# v1.net
KiCad netlist of a schematic drawn in EAGLE
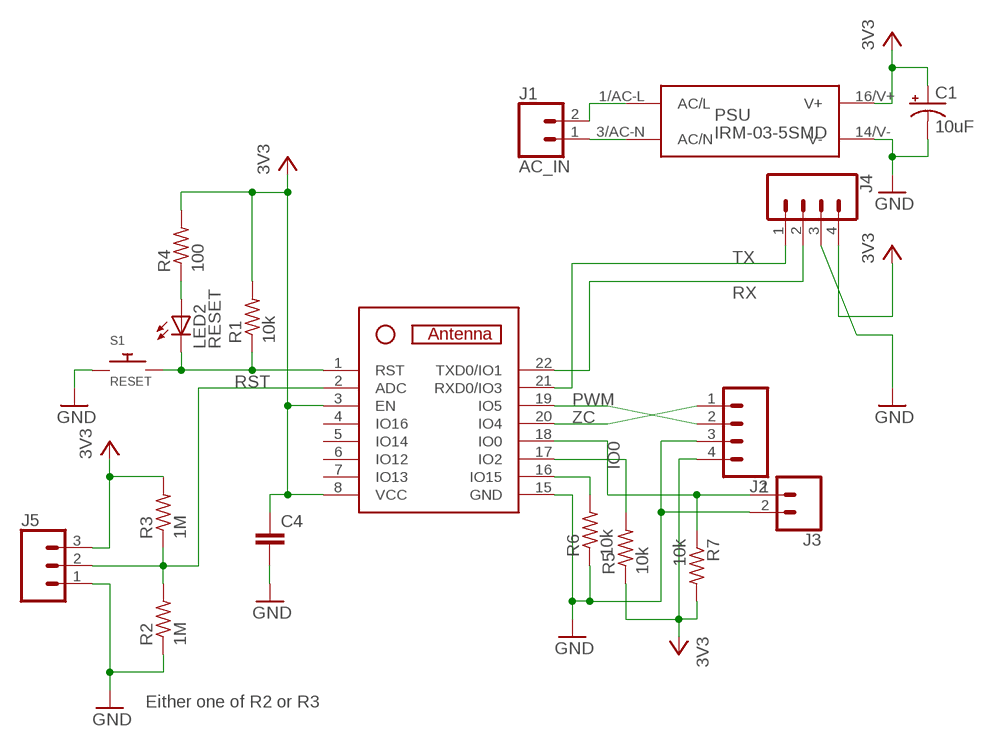
[diagram p0: schematic, sheet 1]

(export (version "E")
  (design (tool "Eeschema 10.0.6"))
  (components
    (comp (ref "C1")
      (value "10uF")
      (footprint "eagle-import:153CLV-0405")
      (libsource (lib "eagle-import") (part "CPOL-US153CLV-0405"))
    )
    (comp (ref "C4")
      (value "C-EUC0805")
      (footprint "eagle-import:C0805")
      (libsource (lib "eagle-import") (part "C-EUC0805"))
    )
    (comp (ref "J1")
      (value "AC_IN")
      (footprint "eagle-import:1X2_5MM_SCREW")
      (libsource (lib "eagle-import") (part "1X2_5MM_SCREW"))
    )
    (comp (ref "J2")
      (value "CONN_04")
      (footprint "eagle-import:1X04")
      (libsource (lib "eagle-import") (part "CONN_04"))
    )
    (comp (ref "J3")
      (value "CONN_02")
      (footprint "eagle-import:1X02")
      (libsource (lib "eagle-import") (part "CONN_02"))
    )
    (comp (ref "J4")
      (value "CONN_04")
      (footprint "eagle-import:1X04")
      (libsource (lib "eagle-import") (part "CONN_04"))
    )
    (comp (ref "J5")
      (value "CONN_03")
      (footprint "eagle-import:1X03")
      (libsource (lib "eagle-import") (part "CONN_03"))
    )
    (comp (ref "LED2")
      (value "RESET")
      (footprint "eagle-import:SML0805")
      (libsource (lib "eagle-import") (part "LEDSML0805"))
    )
    (comp (ref "PSU")
      (value "IRM-03-5SMD")
      (footprint "eagle-import:IRM-03-5S")
      (libsource (lib "eagle-import") (part "IRM-03-5SMD"))
    )
    (comp (ref "R1")
      (value "10k")
      (footprint "eagle-import:R0603")
      (libsource (lib "eagle-import") (part "R-US_R0603"))
    )
    (comp (ref "R2")
      (value "1M")
      (footprint "eagle-import:R0603")
      (libsource (lib "eagle-import") (part "R-US_R0603"))
    )
    (comp (ref "R3")
      (value "1M")
      (footprint "eagle-import:R0603")
      (libsource (lib "eagle-import") (part "R-US_R0603"))
    )
    (comp (ref "R4")
      (value "100")
      (footprint "eagle-import:R0805")
      (libsource (lib "eagle-import") (part "R-US_R0805"))
    )
    (comp (ref "R5")
      (value "10k")
      (footprint "eagle-import:R0603")
      (libsource (lib "eagle-import") (part "R-US_R0603"))
    )
    (comp (ref "R6")
      (value "10k")
      (footprint "eagle-import:R0603")
      (libsource (lib "eagle-import") (part "R-US_R0603"))
    )
    (comp (ref "R7")
      (value "10k")
      (footprint "eagle-import:R0603")
      (libsource (lib "eagle-import") (part "R-US_R0603"))
    )
    (comp (ref "S1")
      (value "RESET")
      (footprint "eagle-import:SMD_BUTTON")
      (libsource (lib "eagle-import") (part "BUTTONSMD"))
    )
    (comp (ref "U1")
      (value "ESP-07")
      (footprint "eagle-import:ESP-07")
      (libsource (lib "eagle-import") (part "ESP-07"))
    )
  )
  (nets
    (net (code "1") (name "/IO0") (class "Default")
      (node (ref "J3") (pin "1") (pinfunction "1_1") (pintype "passive"))
      (node (ref "R7") (pin "1") (pinfunction "1_1") (pintype "passive"))
      (node (ref "U1") (pin "18") (pinfunction "IO0_18") (pintype "bidirectional"))
    )
    (net (code "2") (name "/PWM") (class "Default")
      (node (ref "J2") (pin "2") (pinfunction "2_2") (pintype "passive"))
      (node (ref "U1") (pin "19") (pinfunction "IO5_19") (pintype "bidirectional"))
    )
    (net (code "3") (name "/RST") (class "Default")
      (node (ref "LED2") (pin "C") (pinfunction "C_C") (pintype "passive"))
      (node (ref "R1") (pin "1") (pinfunction "1_1") (pintype "passive"))
      (node (ref "S1") (pin "P$2") (pinfunction "P$2_P$2") (pintype "passive"))
      (node (ref "S1") (pin "P$4") (pinfunction "P$2_P$4") (pintype "passive"))
      (node (ref "U1") (pin "1") (pinfunction "RST_1") (pintype "bidirectional"))
    )
    (net (code "4") (name "/RX") (class "Default")
      (node (ref "J4") (pin "2") (pinfunction "2_2") (pintype "passive"))
      (node (ref "U1") (pin "22") (pinfunction "TXD0/IO1_22") (pintype "bidirectional"))
    )
    (net (code "5") (name "/TX") (class "Default")
      (node (ref "J4") (pin "1") (pinfunction "1_1") (pintype "passive"))
      (node (ref "U1") (pin "21") (pinfunction "RXD0/IO3_21") (pintype "bidirectional"))
    )
    (net (code "6") (name "/ZC") (class "Default")
      (node (ref "J2") (pin "1") (pinfunction "1_1") (pintype "passive"))
      (node (ref "U1") (pin "20") (pinfunction "IO4_20") (pintype "bidirectional"))
    )
    (net (code "7") (name "3V3") (class "Default")
      (node (ref "C1") (pin "+") (pinfunction "+_+") (pintype "passive"))
      (node (ref "C4") (pin "1") (pinfunction "1_1") (pintype "passive"))
      (node (ref "J2") (pin "4") (pinfunction "4_4") (pintype "passive"))
      (node (ref "J4") (pin "4") (pinfunction "4_4") (pintype "passive"))
      (node (ref "J5") (pin "3") (pinfunction "3_3") (pintype "passive"))
      (node (ref "PSU") (pin "16/V+") (pinfunction "V+_16/V+") (pintype "bidirectional"))
      (node (ref "R1") (pin "2") (pinfunction "2_2") (pintype "passive"))
      (node (ref "R3") (pin "2") (pinfunction "2_2") (pintype "passive"))
      (node (ref "R4") (pin "2") (pinfunction "2_2") (pintype "passive"))
      (node (ref "R5") (pin "1") (pinfunction "1_1") (pintype "passive"))
      (node (ref "R7") (pin "2") (pinfunction "2_2") (pintype "passive"))
      (node (ref "U1") (pin "3") (pinfunction "EN_3") (pintype "bidirectional"))
      (node (ref "U1") (pin "8") (pinfunction "VCC_8") (pintype "bidirectional"))
    )
    (net (code "8") (name "GND") (class "Default")
      (node (ref "C1") (pin "-") (pinfunction "-_-") (pintype "passive"))
      (node (ref "C4") (pin "2") (pinfunction "2_2") (pintype "passive"))
      (node (ref "J2") (pin "3") (pinfunction "3_3") (pintype "passive"))
      (node (ref "J3") (pin "2") (pinfunction "2_2") (pintype "passive"))
      (node (ref "J4") (pin "3") (pinfunction "3_3") (pintype "passive"))
      (node (ref "J5") (pin "1") (pinfunction "1_1") (pintype "passive"))
      (node (ref "PSU") (pin "14/V-") (pinfunction "V-_14/V-") (pintype "bidirectional"))
      (node (ref "R2") (pin "1") (pinfunction "1_1") (pintype "passive"))
      (node (ref "R6") (pin "1") (pinfunction "1_1") (pintype "passive"))
      (node (ref "S1") (pin "P$1") (pinfunction "P$1_P$1") (pintype "passive"))
      (node (ref "S1") (pin "P$3") (pinfunction "P$1_P$3") (pintype "passive"))
      (node (ref "U1") (pin "15") (pinfunction "GND_15") (pintype "bidirectional"))
    )
    (net (code "9") (name "Net-(LED2-PadA)") (class "Default")
      (node (ref "LED2") (pin "A") (pinfunction "A_A") (pintype "passive"))
      (node (ref "R4") (pin "1") (pinfunction "1_1") (pintype "passive"))
    )
    (net (code "10") (name "Net-(PSU-AC{slash}L)") (class "Default")
      (node (ref "J1") (pin "2") (pinfunction "2_2") (pintype "passive"))
      (node (ref "PSU") (pin "1/AC-L") (pinfunction "AC/L_1/AC-L") (pintype "bidirectional"))
    )
    (net (code "11") (name "Net-(PSU-AC{slash}N)") (class "Default")
      (node (ref "J1") (pin "1") (pinfunction "1_1") (pintype "passive"))
      (node (ref "PSU") (pin "3/AC-N") (pinfunction "AC/N_3/AC-N") (pintype "bidirectional"))
    )
    (net (code "12") (name "Net-(U1-ADC)") (class "Default")
      (node (ref "J5") (pin "2") (pinfunction "2_2") (pintype "passive"))
      (node (ref "R2") (pin "2") (pinfunction "2_2") (pintype "passive"))
      (node (ref "R3") (pin "1") (pinfunction "1_1") (pintype "passive"))
      (node (ref "U1") (pin "2") (pinfunction "ADC_2") (pintype "bidirectional"))
    )
    (net (code "13") (name "Net-(U1-IO2)") (class "Default")
      (node (ref "R5") (pin "2") (pinfunction "2_2") (pintype "passive"))
      (node (ref "U1") (pin "17") (pinfunction "IO2_17") (pintype "bidirectional"))
    )
    (net (code "14") (name "Net-(U1-IO15)") (class "Default")
      (node (ref "R6") (pin "2") (pinfunction "2_2") (pintype "passive"))
      (node (ref "U1") (pin "16") (pinfunction "IO15_16") (pintype "bidirectional"))
    )
    (net (code "15") (name "unconnected-(U1-IO12-Pad6)") (class "Default")
      (node (ref "U1") (pin "6") (pinfunction "IO12_6") (pintype "bidirectional"))
    )
    (net (code "16") (name "unconnected-(U1-IO13-Pad7)") (class "Default")
      (node (ref "U1") (pin "7") (pinfunction "IO13_7") (pintype "bidirectional"))
    )
    (net (code "17") (name "unconnected-(U1-IO14-Pad5)") (class "Default")
      (node (ref "U1") (pin "5") (pinfunction "IO14_5") (pintype "bidirectional"))
    )
    (net (code "18") (name "unconnected-(U1-IO16-Pad4)") (class "Default")
      (node (ref "U1") (pin "4") (pinfunction "IO16_4") (pintype "bidirectional"))
    )
  )
)
